# GYRO_Test.net
KiCad netlist of a schematic drawn in EasyEDA Pro
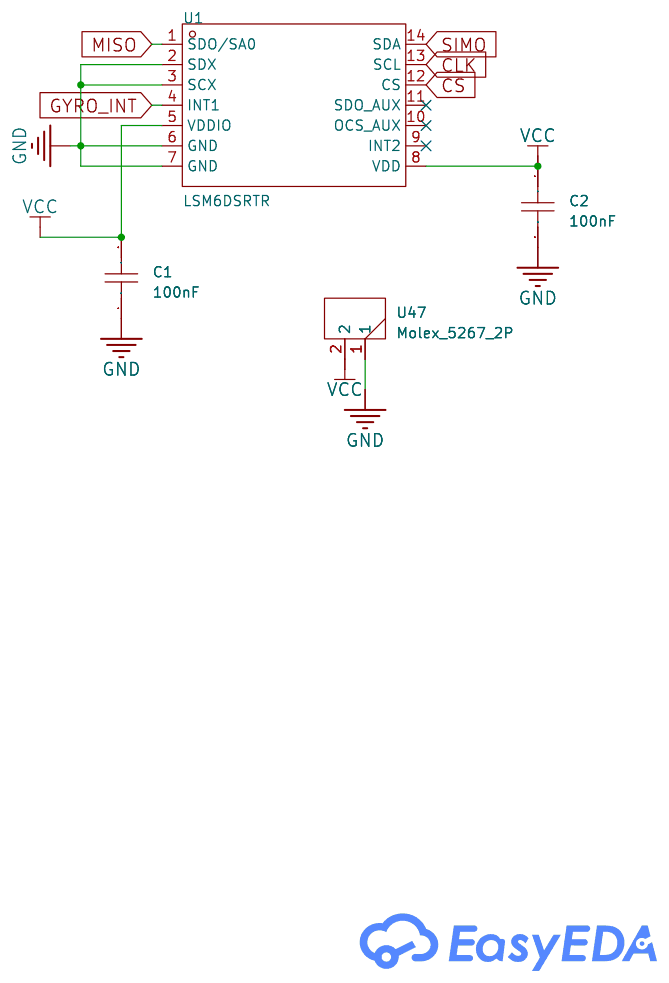
[diagram p0: schematic sheet]

(export (version "E")
  (design (tool "Eeschema 10.0.6"))
  (components
    (comp (ref "C1")
      (value "100nF")
      (footprint "easyedapro:C0603")
      (libsource (lib "easyedapro") (part "CAP"))
    )
    (comp (ref "C2")
      (value "100nF")
      (footprint "easyedapro:C0603")
      (libsource (lib "easyedapro") (part "CAP"))
    )
    (comp (ref "U1")
      (value "LSM6DSRTR")
      (footprint "easyedapro:LGA-14_L3.0-W2.5-P0.50-BR")
      (fields (field (name "Manufacturer") "ST(意法半导体)"))
      (libsource (lib "easyedapro") (part "LSM6DSRTR"))
    )
    (comp (ref "U47")
      (value "Molex_5267_2P")
      (footprint "easyedapro:5267_2P")
      (libsource (lib "easyedapro") (part "Molex_5267_2P"))
    )
  )
  (nets
    (net (code "1") (name "CLK") (class "Default")
      (node (ref "U1") (pin "13") (pinfunction "SCL_13") (pintype "unspecified"))
    )
    (net (code "2") (name "CS") (class "Default")
      (node (ref "U1") (pin "12") (pinfunction "CS_12") (pintype "unspecified"))
    )
    (net (code "3") (name "GND") (class "Default")
      (node (ref "C1") (pin "1") (pinfunction "1_1") (pintype "input"))
      (node (ref "C2") (pin "2") (pinfunction "2_2") (pintype "input"))
      (node (ref "U1") (pin "2") (pinfunction "SDX_2") (pintype "unspecified"))
      (node (ref "U1") (pin "3") (pinfunction "SCX_3") (pintype "unspecified"))
      (node (ref "U1") (pin "6") (pinfunction "GND_6") (pintype "unspecified"))
      (node (ref "U1") (pin "7") (pinfunction "GND_7") (pintype "unspecified"))
      (node (ref "U47") (pin "1") (pinfunction "1_1") (pintype "unspecified"))
    )
    (net (code "4") (name "GYRO_INT") (class "Default")
      (node (ref "U1") (pin "4") (pinfunction "INT1_4") (pintype "unspecified"))
    )
    (net (code "5") (name "MISO") (class "Default")
      (node (ref "U1") (pin "1") (pinfunction "SDO/SA0_1") (pintype "unspecified"))
    )
    (net (code "6") (name "SIMO") (class "Default")
      (node (ref "U1") (pin "14") (pinfunction "SDA_14") (pintype "unspecified"))
    )
    (net (code "7") (name "VCC") (class "Default")
      (node (ref "C1") (pin "2") (pinfunction "2_2") (pintype "input"))
      (node (ref "C2") (pin "1") (pinfunction "1_1") (pintype "input"))
      (node (ref "U1") (pin "5") (pinfunction "VDDIO_5") (pintype "unspecified"))
      (node (ref "U1") (pin "8") (pinfunction "VDD_8") (pintype "unspecified"))
      (node (ref "U47") (pin "2") (pinfunction "2_2") (pintype "unspecified"))
    )
    (net (code "8") (name "unconnected-(U1-INT2-Pad9)") (class "Default")
      (node (ref "U1") (pin "9") (pinfunction "INT2_9") (pintype "unspecified+no_connect"))
    )
    (net (code "9") (name "unconnected-(U1-OCS_AUX-Pad10)") (class "Default")
      (node (ref "U1") (pin "10") (pinfunction "OCS_AUX_10") (pintype "unspecified+no_connect"))
    )
    (net (code "10") (name "unconnected-(U1-SDO_AUX-Pad11)") (class "Default")
      (node (ref "U1") (pin "11") (pinfunction "SDO_AUX_11") (pintype "unspecified+no_connect"))
    )
  )
)
